# OV5647_MIPI_V2_1.net
KiCad netlist of a schematic drawn in Altium Designer
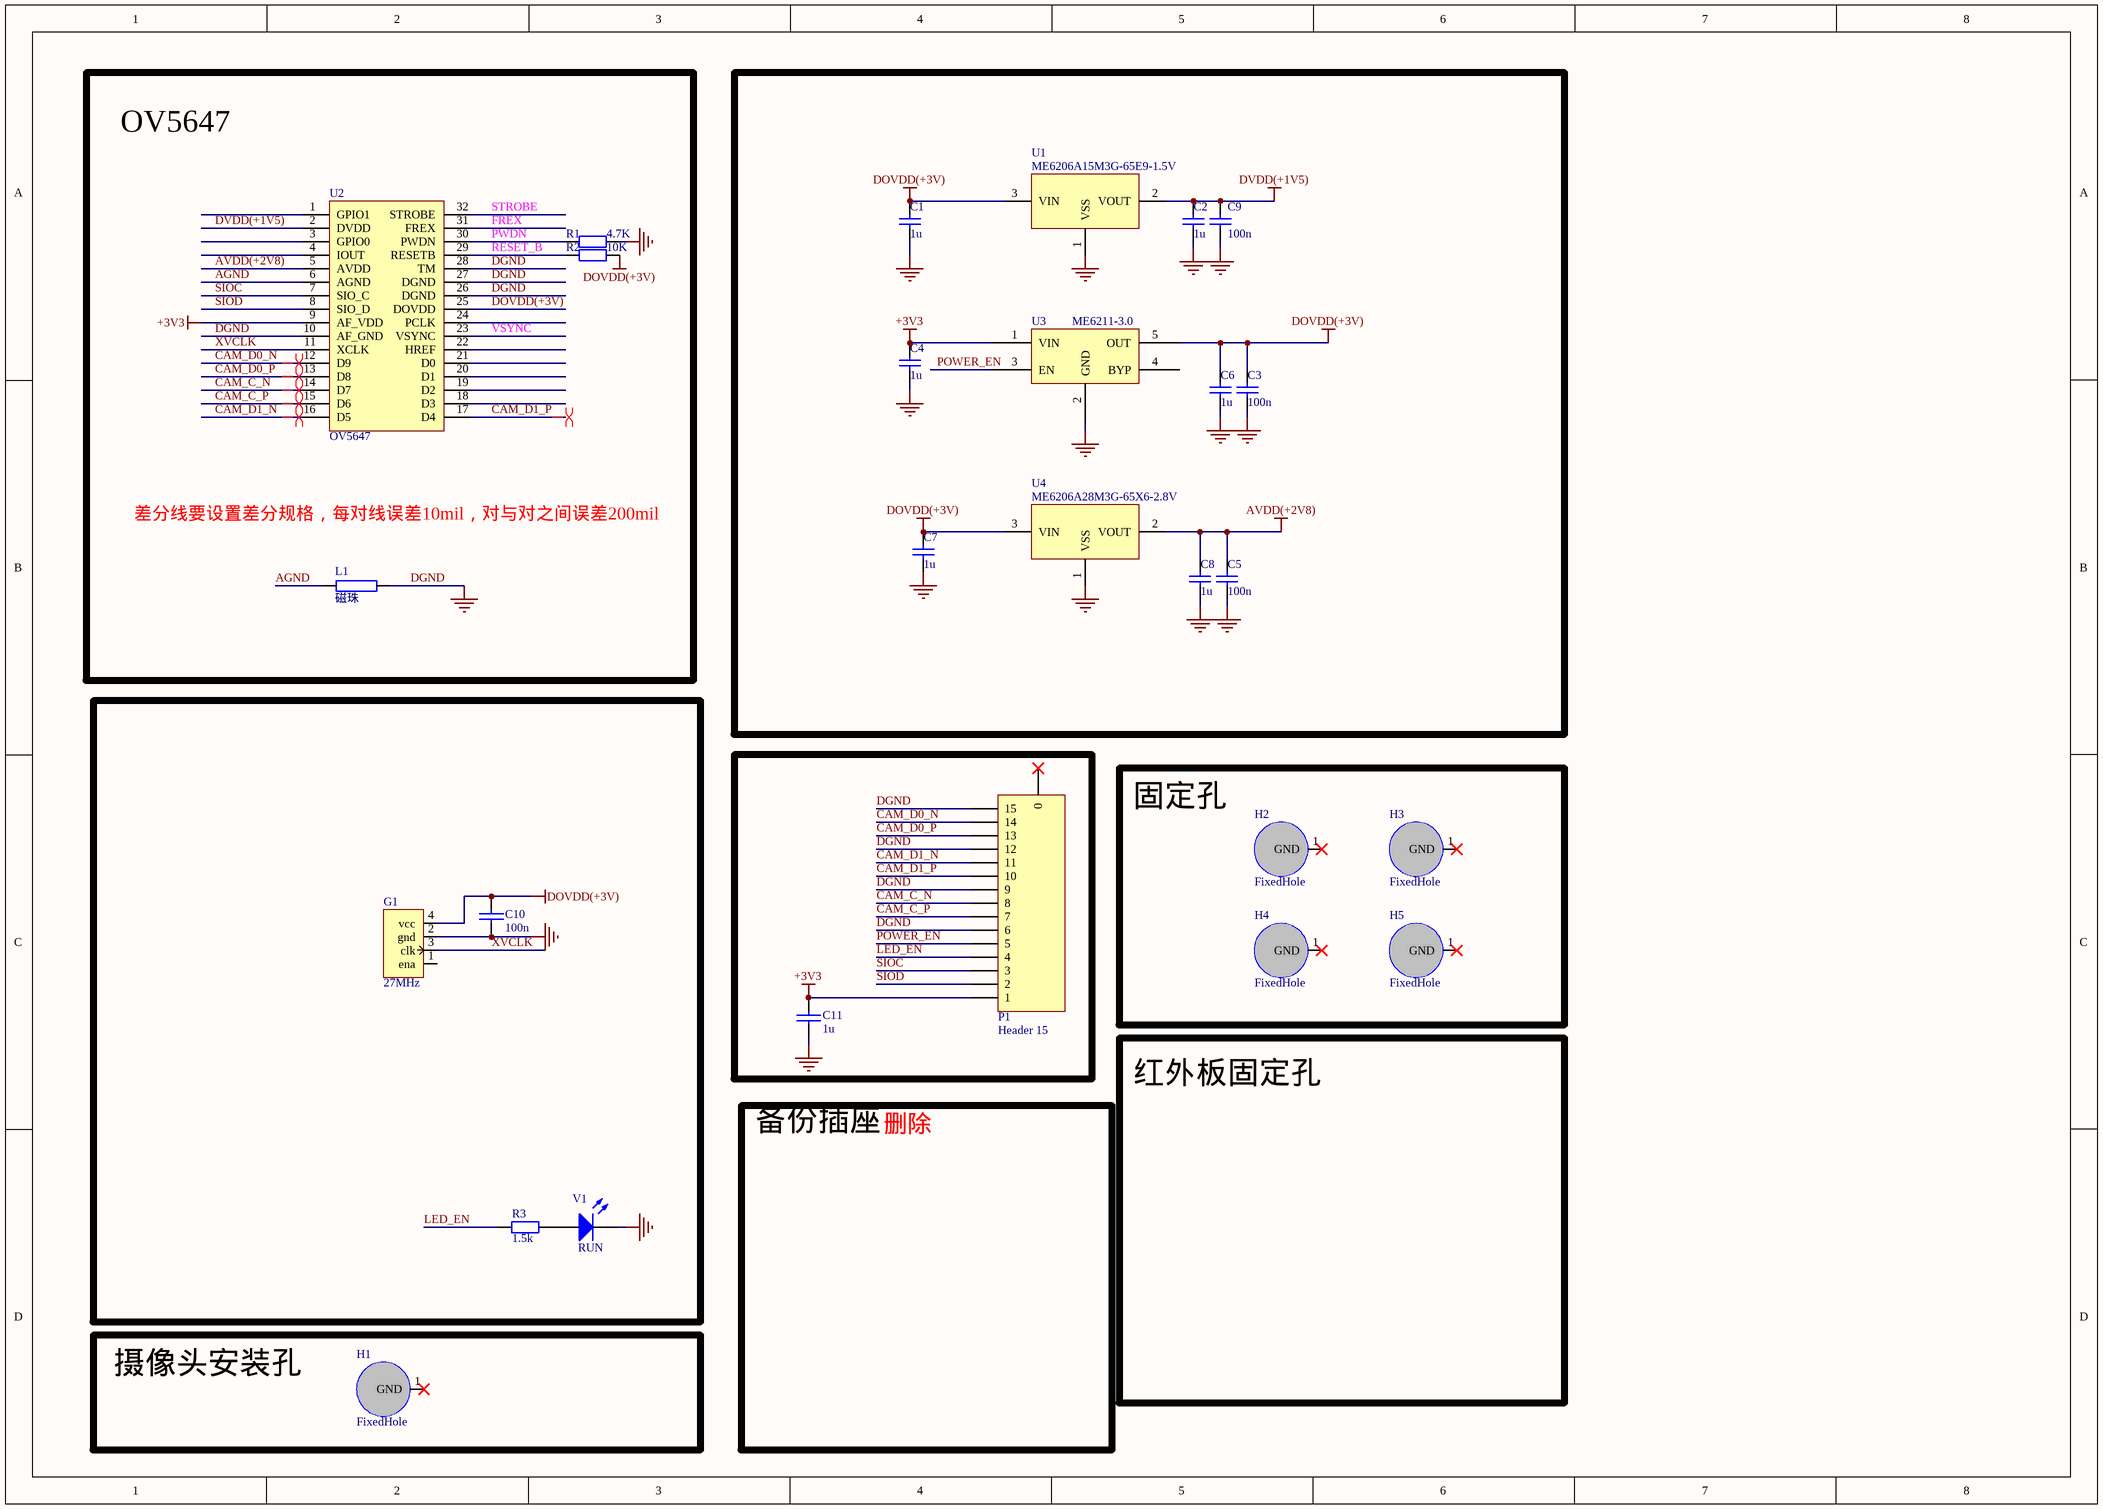
[diagram p0: 摄像头转换板_OV5647_MIPI V2.1.SchDoc]

(export (version "E")
  (design (tool "Eeschema 10.0.6"))
  (components
    (comp (ref "C1")
      (value "1u")
      (footprint "0603S-CAP")
      (description "50V/8.2u/0805")
      (fields (field (name "PUBLISHER") "Altium Limited"))
      (libsource (lib "Miscellaneous Devices") (part "Cap"))
    )
    (comp (ref "C2")
      (value "1u")
      (footprint "0603S-CAP")
      (description "50V/8.2u/0805")
      (fields (field (name "PUBLISHER") "Altium Limited"))
      (libsource (lib "Miscellaneous Devices") (part "Cap"))
    )
    (comp (ref "C3")
      (value "100n")
      (footprint "0603S-CAP")
      (description "50V/8.2u/0805")
      (fields (field (name "PUBLISHER") "Altium Limited"))
      (libsource (lib "Miscellaneous Devices") (part "Cap"))
    )
    (comp (ref "C4")
      (value "1u")
      (footprint "0603S-CAP")
      (description "50V/8.2u/0805")
      (fields (field (name "PUBLISHER") "Altium Limited"))
      (libsource (lib "Miscellaneous Devices") (part "Cap"))
    )
    (comp (ref "C5")
      (value "100n")
      (footprint "0603S-CAP")
      (description "50V/8.2u/0805")
      (fields (field (name "PUBLISHER") "Altium Limited"))
      (libsource (lib "Miscellaneous Devices") (part "Cap"))
    )
    (comp (ref "C6")
      (value "1u")
      (footprint "0603S-CAP")
      (description "50V/8.2u/0805")
      (fields (field (name "PUBLISHER") "Altium Limited"))
      (libsource (lib "Miscellaneous Devices") (part "Cap"))
    )
    (comp (ref "C7")
      (value "1u")
      (footprint "0603S-CAP")
      (description "50V/8.2u/0805")
      (fields (field (name "PUBLISHER") "Altium Limited"))
      (libsource (lib "Miscellaneous Devices") (part "Cap"))
    )
    (comp (ref "C8")
      (value "1u")
      (footprint "0603S-CAP")
      (description "50V/8.2u/0805")
      (fields (field (name "PUBLISHER") "Altium Limited"))
      (libsource (lib "Miscellaneous Devices") (part "Cap"))
    )
    (comp (ref "C9")
      (value "100n")
      (footprint "0603S-CAP")
      (description "50V/8.2u/0805")
      (fields (field (name "PUBLISHER") "Altium Limited"))
      (libsource (lib "Miscellaneous Devices") (part "Cap"))
    )
    (comp (ref "C10")
      (value "100n")
      (footprint "0603S-CAP")
      (description "RC=1206")
      (libsource (lib "*") (part "CAP"))
    )
    (comp (ref "C11")
      (value "1u")
      (footprint "0603S-CAP")
      (description "RC=1206")
      (libsource (lib "*") (part "CAP"))
    )
    (comp (ref "G1") (value "27MHz") (footprint "爱普生晶振3.2×2.5mm") (libsource (lib "*") (part "CTY4-B")))
    (comp (ref "H1")
      (value "FixedHole")
      (footprint "摄像头安装孔_18/20")
      (libsource (lib "ITMS-02调试电缆转接板") (part "固定孔"))
    )
    (comp (ref "H2") (value "FixedHole") (footprint "固定孔") (libsource (lib "ITMS-02调试电缆转接板") (part "固定孔")))
    (comp (ref "H3") (value "FixedHole") (footprint "固定孔") (libsource (lib "ITMS-02调试电缆转接板") (part "固定孔")))
    (comp (ref "H4") (value "FixedHole") (footprint "固定孔") (libsource (lib "ITMS-02调试电缆转接板") (part "固定孔")))
    (comp (ref "H5") (value "FixedHole") (footprint "固定孔") (libsource (lib "ITMS-02调试电缆转接板") (part "固定孔")))
    (comp (ref "L1") (value "磁珠") (footprint "L0603") (libsource (lib "*") (part "RES")))
    (comp (ref "P1")
      (value "Header 15")
      (footprint "OV5647_MIPI")
      (description "Header, 15-Pin")
      (fields (field (name "PUBLISHER") "Altium Limited"))
      (libsource (lib "摄像头转换板_OV5647_MIPI V1.0") (part "Header 15"))
    )
    (comp (ref "R1")
      (value "4.7K")
      (footprint "0603S-RES")
      (description "Resistor")
      (fields (field (name "PUBLISHER") "Altium Limited"))
      (libsource (lib "") (part "Res2_1"))
    )
    (comp (ref "R2")
      (value "10K")
      (footprint "0603S-RES")
      (description "Resistor")
      (fields (field (name "PUBLISHER") "Altium Limited"))
      (libsource (lib "") (part "Res2_1"))
    )
    (comp (ref "R3")
      (value "1.5k")
      (footprint "0603S-RES")
      (description "Resistor")
      (fields (field (name "PUBLISHER") "Altium Limited"))
      (libsource (lib "DM642") (part "Res2"))
    )
    (comp (ref "U1")
      (value "ME6206A15M3G-65E9-1.5V")
      (footprint "SOT23-3")
      (libsource (lib "Schlib1") (part "65e9"))
    )
    (comp (ref "U2") (value "OV5647") (footprint "OV5647") (libsource (lib "Schlib1") (part "OV5647")))
    (comp (ref "U3")
      (value "ME6211-3.0")
      (footprint "SOT23-5")
      (libsource (lib "MT9D112") (part "PAM3101DAB150"))
    )
    (comp (ref "U4")
      (value "ME6206A28M3G-65X6-2.8V")
      (footprint "SOT23-3")
      (libsource (lib "Schlib1") (part "65e9"))
    )
    (comp (ref "V1")
      (value "RUN")
      (footprint "LED-0603")
      (description "Typical INFRARED GaAs LED")
      (fields (field (name "PUBLISHER") "Altium Limited"))
      (libsource (lib "DM642") (part "LED0"))
    )
  )
  (nets
    (net (code "1") (name "+3V3") (class "Default")
      (node (ref "C11") (pin "1") (pintype "passive"))
      (node (ref "C4") (pin "2") (pinfunction "2_2") (pintype "passive"))
      (node (ref "P1") (pin "1") (pinfunction "1_1") (pintype "passive"))
      (node (ref "U2") (pin "9") (pinfunction "AF_VDD_9") (pintype "passive"))
      (node (ref "U3") (pin "1") (pinfunction "VIN_1") (pintype "passive"))
    )
    (net (code "2") (name "/AGND") (class "Default")
      (node (ref "L1") (pin "2") (pinfunction "2_2") (pintype "passive"))
      (node (ref "U2") (pin "6") (pinfunction "AGND_6") (pintype "passive"))
    )
    (net (code "3") (name "/CAM_C_N") (class "Default")
      (node (ref "P1") (pin "8") (pinfunction "8_8") (pintype "passive"))
      (node (ref "U2") (pin "14") (pinfunction "D7_14") (pintype "passive"))
    )
    (net (code "4") (name "/CAM_C_P") (class "Default")
      (node (ref "P1") (pin "7") (pinfunction "7_7") (pintype "passive"))
      (node (ref "U2") (pin "15") (pinfunction "D6_15") (pintype "passive"))
    )
    (net (code "5") (name "/CAM_D0_N") (class "Default")
      (node (ref "P1") (pin "14") (pinfunction "14_14") (pintype "passive"))
      (node (ref "U2") (pin "12") (pinfunction "D9_12") (pintype "passive"))
    )
    (net (code "6") (name "/CAM_D0_P") (class "Default")
      (node (ref "P1") (pin "13") (pinfunction "13_13") (pintype "passive"))
      (node (ref "U2") (pin "13") (pinfunction "D8_13") (pintype "passive"))
    )
    (net (code "7") (name "/CAM_D1_N") (class "Default")
      (node (ref "P1") (pin "11") (pinfunction "11_11") (pintype "passive"))
      (node (ref "U2") (pin "16") (pinfunction "D5_16") (pintype "passive"))
    )
    (net (code "8") (name "/CAM_D1_P") (class "Default")
      (node (ref "P1") (pin "10") (pinfunction "10_10") (pintype "passive"))
      (node (ref "U2") (pin "17") (pinfunction "D4_17") (pintype "passive"))
    )
    (net (code "9") (name "/FREX") (class "Default")
      (node (ref "U2") (pin "31") (pinfunction "FREX_31") (pintype "passive"))
    )
    (net (code "10") (name "/LED_EN") (class "Default")
      (node (ref "P1") (pin "4") (pinfunction "4_4") (pintype "passive"))
      (node (ref "R3") (pin "1") (pinfunction "1_1") (pintype "passive"))
    )
    (net (code "11") (name "/POWER_EN") (class "Default")
      (node (ref "P1") (pin "5") (pinfunction "5_5") (pintype "passive"))
      (node (ref "U3") (pin "3") (pinfunction "EN_3") (pintype "passive"))
    )
    (net (code "12") (name "/PWDN") (class "Default")
      (node (ref "R1") (pin "2") (pinfunction "2_2") (pintype "passive"))
      (node (ref "U2") (pin "30") (pinfunction "PWDN_30") (pintype "passive"))
    )
    (net (code "13") (name "/RESET_B") (class "Default")
      (node (ref "R2") (pin "2") (pinfunction "2_2") (pintype "passive"))
      (node (ref "U2") (pin "29") (pinfunction "RESETB_29") (pintype "passive"))
    )
    (net (code "14") (name "/SIOC") (class "Default")
      (node (ref "P1") (pin "3") (pinfunction "3_3") (pintype "passive"))
      (node (ref "U2") (pin "7") (pinfunction "SIO_C_7") (pintype "passive"))
    )
    (net (code "15") (name "/SIOD") (class "Default")
      (node (ref "P1") (pin "2") (pinfunction "2_2") (pintype "passive"))
      (node (ref "U2") (pin "8") (pinfunction "SIO_D_8") (pintype "passive"))
    )
    (net (code "16") (name "/STROBE") (class "Default")
      (node (ref "U2") (pin "32") (pinfunction "STROBE_32") (pintype "passive"))
    )
    (net (code "17") (name "/VSYNC") (class "Default")
      (node (ref "U2") (pin "23") (pinfunction "VSYNC_23") (pintype "passive"))
    )
    (net (code "18") (name "/XVCLK") (class "Default")
      (node (ref "G1") (pin "3") (pinfunction "clk_3") (pintype "passive"))
      (node (ref "U2") (pin "11") (pinfunction "XCLK_11") (pintype "passive"))
    )
    (net (code "19") (name "AVDD(+2V8)") (class "Default")
      (node (ref "C5") (pin "2") (pinfunction "2_2") (pintype "passive"))
      (node (ref "C8") (pin "2") (pinfunction "2_2") (pintype "passive"))
      (node (ref "U2") (pin "5") (pinfunction "AVDD_5") (pintype "passive"))
      (node (ref "U4") (pin "2") (pinfunction "VOUT_2") (pintype "passive"))
    )
    (net (code "20") (name "DGND") (class "Default")
      (node (ref "C1") (pin "1") (pinfunction "1_1") (pintype "passive"))
      (node (ref "C10") (pin "2") (pintype "passive"))
      (node (ref "C11") (pin "2") (pintype "passive"))
      (node (ref "C2") (pin "1") (pinfunction "1_1") (pintype "passive"))
      (node (ref "C3") (pin "1") (pinfunction "1_1") (pintype "passive"))
      (node (ref "C4") (pin "1") (pinfunction "1_1") (pintype "passive"))
      (node (ref "C5") (pin "1") (pinfunction "1_1") (pintype "passive"))
      (node (ref "C6") (pin "1") (pinfunction "1_1") (pintype "passive"))
      (node (ref "C7") (pin "1") (pinfunction "1_1") (pintype "passive"))
      (node (ref "C8") (pin "1") (pinfunction "1_1") (pintype "passive"))
      (node (ref "C9") (pin "1") (pinfunction "1_1") (pintype "passive"))
      (node (ref "G1") (pin "2") (pinfunction "gnd_2") (pintype "power_in"))
      (node (ref "L1") (pin "1") (pinfunction "1_1") (pintype "passive"))
      (node (ref "P1") (pin "12") (pinfunction "12_12") (pintype "passive"))
      (node (ref "P1") (pin "15") (pinfunction "15_15") (pintype "passive"))
      (node (ref "P1") (pin "6") (pinfunction "6_6") (pintype "passive"))
      (node (ref "P1") (pin "9") (pinfunction "9_9") (pintype "passive"))
      (node (ref "R1") (pin "1") (pinfunction "1_1") (pintype "passive"))
      (node (ref "U1") (pin "1") (pinfunction "VSS_1") (pintype "passive"))
      (node (ref "U2") (pin "10") (pinfunction "AF_GND_10") (pintype "passive"))
      (node (ref "U2") (pin "26") (pinfunction "DGND_26") (pintype "passive"))
      (node (ref "U2") (pin "27") (pinfunction "DGND_27") (pintype "passive"))
      (node (ref "U2") (pin "28") (pinfunction "TM_28") (pintype "passive"))
      (node (ref "U3") (pin "2") (pinfunction "GND_2") (pintype "passive"))
      (node (ref "U4") (pin "1") (pinfunction "VSS_1") (pintype "passive"))
      (node (ref "V1") (pin "2") (pinfunction "K_2") (pintype "passive"))
    )
    (net (code "21") (name "DOVDD(+3V)") (class "Default")
      (node (ref "C1") (pin "2") (pinfunction "2_2") (pintype "passive"))
      (node (ref "C10") (pin "1") (pintype "passive"))
      (node (ref "C3") (pin "2") (pinfunction "2_2") (pintype "passive"))
      (node (ref "C6") (pin "2") (pinfunction "2_2") (pintype "passive"))
      (node (ref "C7") (pin "2") (pinfunction "2_2") (pintype "passive"))
      (node (ref "G1") (pin "4") (pinfunction "vcc_4") (pintype "power_in"))
      (node (ref "R2") (pin "1") (pinfunction "1_1") (pintype "passive"))
      (node (ref "U1") (pin "3") (pinfunction "VIN_3") (pintype "passive"))
      (node (ref "U2") (pin "25") (pinfunction "DOVDD_25") (pintype "passive"))
      (node (ref "U3") (pin "5") (pinfunction "OUT_5") (pintype "passive"))
      (node (ref "U4") (pin "3") (pinfunction "VIN_3") (pintype "passive"))
    )
    (net (code "22") (name "DVDD(+1V5)") (class "Default")
      (node (ref "C2") (pin "2") (pinfunction "2_2") (pintype "passive"))
      (node (ref "C9") (pin "2") (pinfunction "2_2") (pintype "passive"))
      (node (ref "U1") (pin "2") (pinfunction "VOUT_2") (pintype "passive"))
      (node (ref "U2") (pin "2") (pinfunction "DVDD_2") (pintype "passive"))
    )
    (net (code "23") (name "Net-(V1-A)") (class "Default")
      (node (ref "R3") (pin "2") (pinfunction "2_2") (pintype "passive"))
      (node (ref "V1") (pin "1") (pinfunction "A_1") (pintype "passive"))
    )
    (net (code "24") (name "unconnected-(G1-ena-Pad1)") (class "Default")
      (node (ref "G1") (pin "1") (pinfunction "ena_1") (pintype "passive"))
    )
    (net (code "25") (name "unconnected-(H1-GND-Pad1)") (class "Default")
      (node (ref "H1") (pin "1") (pinfunction "GND_1") (pintype "passive+no_connect"))
    )
    (net (code "26") (name "unconnected-(H2-GND-Pad1)") (class "Default")
      (node (ref "H2") (pin "1") (pinfunction "GND_1") (pintype "passive+no_connect"))
    )
    (net (code "27") (name "unconnected-(H3-GND-Pad1)") (class "Default")
      (node (ref "H3") (pin "1") (pinfunction "GND_1") (pintype "passive+no_connect"))
    )
    (net (code "28") (name "unconnected-(H4-GND-Pad1)") (class "Default")
      (node (ref "H4") (pin "1") (pinfunction "GND_1") (pintype "passive+no_connect"))
    )
    (net (code "29") (name "unconnected-(H5-GND-Pad1)") (class "Default")
      (node (ref "H5") (pin "1") (pinfunction "GND_1") (pintype "passive+no_connect"))
    )
    (net (code "30") (name "unconnected-(P1-Pad0)") (class "Default")
      (node (ref "P1") (pin "0") (pinfunction "0_0") (pintype "passive+no_connect"))
    )
    (net (code "31") (name "unconnected-(U2-D0-Pad21)") (class "Default")
      (node (ref "U2") (pin "21") (pinfunction "D0_21") (pintype "passive"))
    )
    (net (code "32") (name "unconnected-(U2-D1-Pad20)") (class "Default")
      (node (ref "U2") (pin "20") (pinfunction "D1_20") (pintype "passive"))
    )
    (net (code "33") (name "unconnected-(U2-D2-Pad19)") (class "Default")
      (node (ref "U2") (pin "19") (pinfunction "D2_19") (pintype "passive"))
    )
    (net (code "34") (name "unconnected-(U2-D3-Pad18)") (class "Default")
      (node (ref "U2") (pin "18") (pinfunction "D3_18") (pintype "passive"))
    )
    (net (code "35") (name "unconnected-(U2-GPIO0-Pad3)") (class "Default")
      (node (ref "U2") (pin "3") (pinfunction "GPIO0_3") (pintype "passive"))
    )
    (net (code "36") (name "unconnected-(U2-GPIO1-Pad1)") (class "Default")
      (node (ref "U2") (pin "1") (pinfunction "GPIO1_1") (pintype "passive"))
    )
    (net (code "37") (name "unconnected-(U2-HREF-Pad22)") (class "Default")
      (node (ref "U2") (pin "22") (pinfunction "HREF_22") (pintype "passive"))
    )
    (net (code "38") (name "unconnected-(U2-IOUT-Pad4)") (class "Default")
      (node (ref "U2") (pin "4") (pinfunction "IOUT_4") (pintype "passive"))
    )
    (net (code "39") (name "unconnected-(U2-PCLK-Pad24)") (class "Default")
      (node (ref "U2") (pin "24") (pinfunction "PCLK_24") (pintype "passive"))
    )
    (net (code "40") (name "unconnected-(U3-BYP-Pad4)") (class "Default")
      (node (ref "U3") (pin "4") (pinfunction "BYP_4") (pintype "passive"))
    )
  )
)
